# Dual_Power.net
KiCad netlist of a schematic drawn in Altium Designer
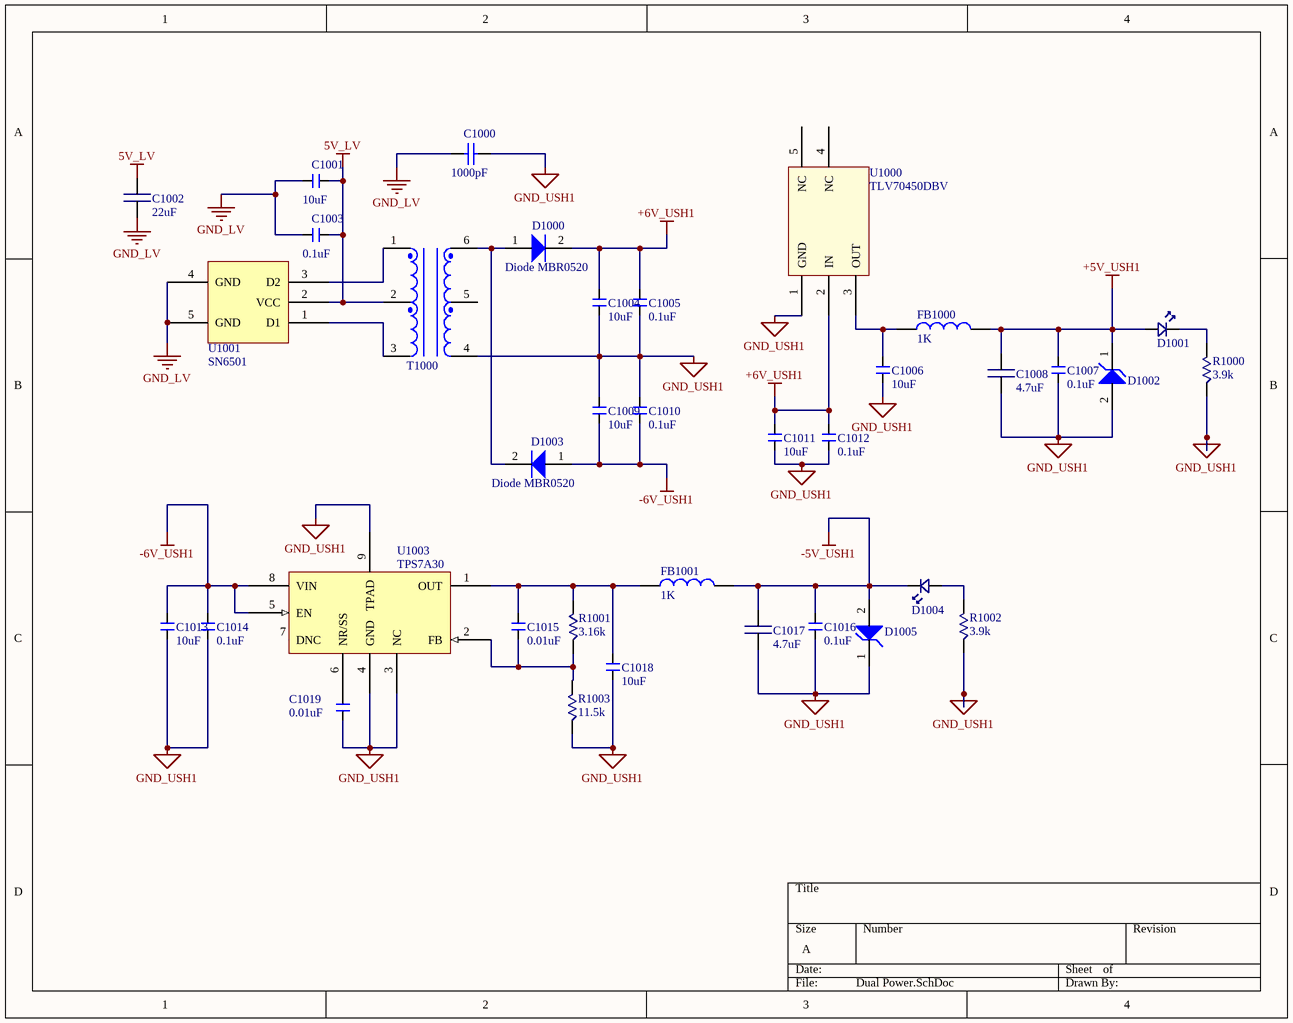
[diagram p0: Dual Power.SchDoc]

(export (version "E")
  (design (tool "Eeschema 10.0.6"))
  (components
    (comp (ref "C1000")
      (value "1000pF")
      (footprint "RAD-0.3")
      (description "CAP CER 1000PF 1KV Y5P RADIAL")
      (fields
        (field (name "PART") "1251PH-ND")
        (field (name "Comment") "Cap TH")
        (field (name "PUBLISHER") "Altium Limited")
      )
      (libsource (lib "Miscellaneous Devices") (part "Cap"))
    )
    (comp (ref "C1001")
      (value "10uF")
      (footprint "0603 (1608 Metric)")
      (description "CAP CER 10UF 35V X5R 0805")
      (fields (field (name "PART") "490-10515-1-ND") (field (name "Comment") "Cap 0603_new"))
      (libsource (lib "Library_Microgrid") (part "Cap 0603_new"))
    )
    (comp (ref "C1002")
      (value "22uF")
      (footprint "0805 (2012 metric)")
      (description "CAP CER 22UF 35V X5R 0805")
      (fields (field (name "PART") "445-14428-1-ND") (field (name "Comment") "Cap 0805"))
      (libsource (lib "Library_Microgrid") (part "Cap 0805"))
    )
    (comp (ref "C1003")
      (value "0.1uF")
      (footprint "0603 (1608 Metric)")
      (description "CAP CER 0.1UF 50V Y5V 0603")
      (fields (field (name "PART") "311-1343-6-ND") (field (name "Comment") "Cap 0603_new"))
      (libsource (lib "Library_Microgrid") (part "Cap 0603_new"))
    )
    (comp (ref "C1004")
      (value "10uF")
      (footprint "0603 (1608 Metric)")
      (description "CAP CER 10UF 35V X5R 0805")
      (fields (field (name "PART") "490-10515-1-ND") (field (name "Comment") "Cap 0603_new"))
      (libsource (lib "Library_Microgrid") (part "Cap 0603_new"))
    )
    (comp (ref "C1005")
      (value "0.1uF")
      (footprint "0603 (1608 Metric)")
      (description "CAP CER 0.1UF 50V Y5V 0603")
      (fields (field (name "PART") "311-1343-6-ND") (field (name "Comment") "Cap 0603_new"))
      (libsource (lib "Library_Microgrid") (part "Cap 0603_new"))
    )
    (comp (ref "C1006")
      (value "10uF")
      (footprint "0603 (1608 Metric)")
      (description "CAP CER 10UF 35V X5R 0805")
      (fields (field (name "PART") "490-10515-1-ND") (field (name "Comment") "Cap 0603_new"))
      (libsource (lib "Library_Microgrid") (part "Cap 0603_new"))
    )
    (comp (ref "C1007")
      (value "0.1uF")
      (footprint "0603 (1608 Metric)")
      (description "CAP CER 0.1UF 50V Y5V 0603")
      (fields (field (name "PART") "311-1343-6-ND") (field (name "Comment") "Cap 0603_new"))
      (libsource (lib "Library_Microgrid") (part "Cap 0603_new"))
    )
    (comp (ref "C1008")
      (value "4.7uF")
      (footprint "0805 (2012 metric)")
      (description "CAP CER 4.7UF 50V X5R 0805")
      (fields (field (name "PART") "445-5980-1-ND") (field (name "Comment") "Cap 0805"))
      (libsource (lib "Library_Microgrid") (part "Cap 0805"))
    )
    (comp (ref "C1009")
      (value "10uF")
      (footprint "0603 (1608 Metric)")
      (description "CAP CER 10UF 35V X5R 0805")
      (fields (field (name "PART") "490-10515-1-ND") (field (name "Comment") "Cap 0603_new"))
      (libsource (lib "Library_Microgrid") (part "Cap 0603_new"))
    )
    (comp (ref "C1010")
      (value "0.1uF")
      (footprint "0603 (1608 Metric)")
      (description "CAP CER 0.1UF 50V Y5V 0603")
      (fields (field (name "PART") "311-1343-6-ND") (field (name "Comment") "Cap 0603_new"))
      (libsource (lib "Library_Microgrid") (part "Cap 0603_new"))
    )
    (comp (ref "C1011")
      (value "10uF")
      (footprint "0603 (1608 Metric)")
      (description "CAP CER 10UF 35V X5R 0805")
      (fields (field (name "PART") "490-10515-1-ND") (field (name "Comment") "Cap 0603_new"))
      (libsource (lib "Library_Microgrid") (part "Cap 0603_new"))
    )
    (comp (ref "C1012")
      (value "0.1uF")
      (footprint "0603 (1608 Metric)")
      (description "CAP CER 0.1UF 50V Y5V 0603")
      (fields (field (name "PART") "311-1343-6-ND") (field (name "Comment") "Cap 0603_new"))
      (libsource (lib "Library_Microgrid") (part "Cap 0603_new"))
    )
    (comp (ref "C1013")
      (value "10uF")
      (footprint "0603 (1608 Metric)")
      (description "CAP CER 10UF 35V X5R 0805")
      (fields (field (name "PART") "490-10515-1-ND") (field (name "Comment") "Cap 0603_new"))
      (libsource (lib "Library_Microgrid") (part "Cap 0603_new"))
    )
    (comp (ref "C1014")
      (value "0.1uF")
      (footprint "0603 (1608 Metric)")
      (description "CAP CER 0.1UF 50V Y5V 0603")
      (fields (field (name "PART") "311-1343-6-ND") (field (name "Comment") "Cap 0603_new"))
      (libsource (lib "Library_Microgrid") (part "Cap 0603_new"))
    )
    (comp (ref "C1015")
      (value "0.01uF")
      (footprint "0603 (1608 Metric)")
      (description "CAP CER 10000PF 100V X7R 0603")
      (fields (field (name "PART") "478-7418-1-ND") (field (name "Comment") "Cap 0603_new"))
      (libsource (lib "Library_Microgrid") (part "Cap 0603_new"))
    )
    (comp (ref "C1016")
      (value "0.1uF")
      (footprint "0603 (1608 Metric)")
      (description "CAP CER 0.1UF 50V Y5V 0603")
      (fields (field (name "PART") "311-1343-6-ND") (field (name "Comment") "Cap 0603_new"))
      (libsource (lib "Library_Microgrid") (part "Cap 0603_new"))
    )
    (comp (ref "C1017")
      (value "4.7uF")
      (footprint "0805 (2012 metric)")
      (description "CAP CER 4.7UF 50V X5R 0805")
      (fields (field (name "PART") "445-5980-1-ND") (field (name "Comment") "Cap 0805"))
      (libsource (lib "Library_Microgrid") (part "Cap 0805"))
    )
    (comp (ref "C1018")
      (value "10uF")
      (footprint "0603 (1608 Metric)")
      (description "CAP CER 10UF 35V X5R 0805")
      (fields (field (name "PART") "490-10515-1-ND") (field (name "Comment") "Cap 0603_new"))
      (libsource (lib "Library_Microgrid") (part "Cap 0603_new"))
    )
    (comp (ref "C1019")
      (value "0.01uF")
      (footprint "0603 (1608 Metric)")
      (description "CAP CER 10000PF 100V X7R 0603")
      (fields (field (name "PART") "478-7418-1-ND") (field (name "Comment") "Cap 0603_new"))
      (libsource (lib "Library_Microgrid") (part "Cap 0603_new"))
    )
    (comp (ref "D1000")
      (value "Diode MBR0520")
      (footprint "SOD-123")
      (description "DIODE SCHOTTKY 20V 500MA SOD123")
      (fields (field (name "PART") "MBR0520LT1GOSCT-ND"))
      (libsource (lib "Library_Microgrid") (part "Diode MBR0520"))
    )
    (comp (ref "D1001")
      (value "LED")
      (footprint "0805 (2012 Metric) Diode")
      (description "LED 0805")
      (libsource (lib "Library_Microgrid") (part "LED"))
    )
    (comp (ref "D1002")
      (value "Diode Zener POWERDI123")
      (footprint "POWERDI")
      (description "DIODE ZENER POWERDI123")
      (libsource (lib "Library_Microgrid") (part "Diode Zener POWERDI123"))
    )
    (comp (ref "D1003")
      (value "Diode MBR0520")
      (footprint "SOD-123")
      (description "DIODE SCHOTTKY 20V 500MA SOD123")
      (fields (field (name "PART") "MBR0520LT1GOSCT-ND"))
      (libsource (lib "Library_Microgrid") (part "Diode MBR0520"))
    )
    (comp (ref "D1004")
      (value "LED")
      (footprint "0805 (2012 Metric) Diode")
      (description "LED 0805")
      (libsource (lib "Library_Microgrid") (part "LED"))
    )
    (comp (ref "D1005")
      (value "Diode Zener POWERDI123")
      (footprint "POWERDI")
      (description "DIODE ZENER POWERDI123")
      (libsource (lib "Library_Microgrid") (part "Diode Zener POWERDI123"))
    )
    (comp (ref "FB1000")
      (value "1K")
      (footprint "0603 (1608 Metric)")
      (description "FERRITE BEAD 1 KOHM 0603 1LN")
      (fields (field (name "PART") "445-8672-1-ND") (field (name "Comment") "Ferrite bead"))
      (libsource (lib "Library_Microgrid") (part "Ferrite bead"))
    )
    (comp (ref "FB1001")
      (value "1K")
      (footprint "0603 (1608 Metric)")
      (description "FERRITE BEAD 1 KOHM 0603 1LN")
      (fields (field (name "PART") "445-8672-1-ND") (field (name "Comment") "Ferrite bead"))
      (libsource (lib "Library_Microgrid") (part "Ferrite bead"))
    )
    (comp (ref "R1000")
      (value "3.9k")
      (footprint "0603 (1608 Metric)")
      (description "RES SMD 3.9K OHM 5% 1/10W 0603")
      (fields (field (name "PART") "541-3.9KGCT-ND") (field (name "Comment") "Resistor 0603"))
      (libsource (lib "Library_Microgrid") (part "Resistor 0603"))
    )
    (comp (ref "R1001")
      (value "3.16k")
      (footprint "0603 (1608 Metric)")
      (description "RES SMD 3.16K OHM 1% 1/10W 0603")
      (fields (field (name "PART") "311-3.16KHRCT-ND") (field (name "Comment") "Resistor 0603"))
      (libsource (lib "Library_Microgrid") (part "Resistor 0603"))
    )
    (comp (ref "R1002")
      (value "3.9k")
      (footprint "0603 (1608 Metric)")
      (description "RES SMD 3.9K OHM 5% 1/10W 0603")
      (fields (field (name "PART") "541-3.9KGCT-ND") (field (name "Comment") "Resistor 0603"))
      (libsource (lib "Library_Microgrid") (part "Resistor 0603"))
    )
    (comp (ref "R1003")
      (value "11.5k")
      (footprint "0603 (1608 Metric)")
      (description "RES SMD 11.5K OHM 1% 1/10W 0603")
      (fields (field (name "PART") "541-11.5KHCT-ND") (field (name "Comment") "Resistor 0603"))
      (libsource (lib "Library_Microgrid") (part "Resistor 0603"))
    )
    (comp (ref "T1000")
      (value "750313769")
      (footprint "Xmr SN6501")
      (description "TRANSFORMER SMD TR1.7 SN6501")
      (fields (field (name "PART") "1297-1107-1-ND"))
      (libsource (lib "Library_Microgrid") (part "750313769"))
    )
    (comp (ref "U1000")
      (value "TLV70450DBV")
      (footprint "SOT23-5")
      (description "IC REG LDO 5V 0.15A SOT23-5")
      (fields (field (name "PART") "296-39287-1-ND"))
      (libsource (lib "Library_Microgrid") (part "TLV70450DBV"))
    )
    (comp (ref "U1001")
      (value "SN6501")
      (footprint "SOT23-5")
      (description "IC REG CONV PWR SUPPLIES SOT23-5")
      (libsource (lib "Library_Microgrid") (part "SN6501"))
    )
    (comp (ref "U1003")
      (value "TPS7A30")
      (footprint "8-TSSOP")
      (description "IC REG LDO NEG ADJ 0.2A 8MSOP")
      (fields (field (name "PART") "296-27750-1-ND"))
      (libsource (lib "Library_Microgrid") (part "TPS7A30"))
    )
  )
  (nets
    (net (code "1") (name "+5V_USH1") (class "Default")
      (node (ref "C1007") (pin "2") (pinfunction "OUT_2") (pintype "passive"))
      (node (ref "C1008") (pin "2") (pinfunction "OUT_2") (pintype "passive"))
      (node (ref "D1001") (pin "A") (pinfunction "A_A") (pintype "passive"))
      (node (ref "D1002") (pin "1") (pinfunction "Anode_1") (pintype "passive"))
      (node (ref "FB1000") (pin "2") (pinfunction "OUT_2") (pintype "passive"))
    )
    (net (code "2") (name "+6V_USH1") (class "Default")
      (node (ref "C1004") (pin "2") (pinfunction "OUT_2") (pintype "passive"))
      (node (ref "C1005") (pin "2") (pinfunction "OUT_2") (pintype "passive"))
      (node (ref "C1011") (pin "2") (pinfunction "OUT_2") (pintype "passive"))
      (node (ref "C1012") (pin "2") (pinfunction "OUT_2") (pintype "passive"))
      (node (ref "D1000") (pin "2") (pinfunction "Anode_2") (pintype "passive"))
      (node (ref "U1000") (pin "2") (pinfunction "IN_2") (pintype "passive"))
    )
    (net (code "3") (name "-5V_USH1") (class "Default")
      (node (ref "C1016") (pin "2") (pinfunction "OUT_2") (pintype "passive"))
      (node (ref "C1017") (pin "2") (pinfunction "OUT_2") (pintype "passive"))
      (node (ref "D1004") (pin "K") (pinfunction "K_K") (pintype "passive"))
      (node (ref "D1005") (pin "2") (pinfunction "Anode_2") (pintype "passive"))
      (node (ref "FB1001") (pin "2") (pinfunction "OUT_2") (pintype "passive"))
    )
    (net (code "4") (name "-6V_USH1") (class "Default")
      (node (ref "C1009") (pin "1") (pinfunction "OUT_1") (pintype "passive"))
      (node (ref "C1010") (pin "1") (pinfunction "OUT_1") (pintype "passive"))
      (node (ref "C1013") (pin "2") (pinfunction "OUT_2") (pintype "passive"))
      (node (ref "C1014") (pin "2") (pinfunction "OUT_2") (pintype "passive"))
      (node (ref "D1003") (pin "1") (pinfunction "Anode_1") (pintype "passive"))
      (node (ref "U1003") (pin "5") (pinfunction "EN_5") (pintype "input"))
      (node (ref "U1003") (pin "8") (pinfunction "VIN_8") (pintype "power_in"))
    )
    (net (code "5") (name "5V_LV") (class "Default")
      (node (ref "C1001") (pin "2") (pinfunction "OUT_2") (pintype "passive"))
      (node (ref "C1002") (pin "2") (pinfunction "OUT_2") (pintype "passive"))
      (node (ref "C1003") (pin "2") (pinfunction "OUT_2") (pintype "passive"))
      (node (ref "T1000") (pin "2") (pinfunction "1_2") (pintype "passive"))
      (node (ref "U1001") (pin "2") (pinfunction "VCC_2") (pintype "passive"))
    )
    (net (code "6") (name "GND_LV") (class "Default")
      (node (ref "C1000") (pin "1") (pinfunction "1_1") (pintype "passive"))
      (node (ref "C1001") (pin "1") (pinfunction "OUT_1") (pintype "passive"))
      (node (ref "C1002") (pin "1") (pinfunction "OUT_1") (pintype "passive"))
      (node (ref "C1003") (pin "1") (pinfunction "OUT_1") (pintype "passive"))
      (node (ref "U1001") (pin "4") (pinfunction "GND_4") (pintype "passive"))
      (node (ref "U1001") (pin "5") (pinfunction "GND_5") (pintype "passive"))
    )
    (net (code "7") (name "GND_USH1") (class "Default")
      (node (ref "C1000") (pin "2") (pinfunction "2_2") (pintype "passive"))
      (node (ref "C1004") (pin "1") (pinfunction "OUT_1") (pintype "passive"))
      (node (ref "C1005") (pin "1") (pinfunction "OUT_1") (pintype "passive"))
      (node (ref "C1006") (pin "1") (pinfunction "OUT_1") (pintype "passive"))
      (node (ref "C1007") (pin "1") (pinfunction "OUT_1") (pintype "passive"))
      (node (ref "C1008") (pin "1") (pinfunction "OUT_1") (pintype "passive"))
      (node (ref "C1009") (pin "2") (pinfunction "OUT_2") (pintype "passive"))
      (node (ref "C1010") (pin "2") (pinfunction "OUT_2") (pintype "passive"))
      (node (ref "C1011") (pin "1") (pinfunction "OUT_1") (pintype "passive"))
      (node (ref "C1012") (pin "1") (pinfunction "OUT_1") (pintype "passive"))
      (node (ref "C1013") (pin "1") (pinfunction "OUT_1") (pintype "passive"))
      (node (ref "C1014") (pin "1") (pinfunction "OUT_1") (pintype "passive"))
      (node (ref "C1016") (pin "1") (pinfunction "OUT_1") (pintype "passive"))
      (node (ref "C1017") (pin "1") (pinfunction "OUT_1") (pintype "passive"))
      (node (ref "C1018") (pin "1") (pinfunction "OUT_1") (pintype "passive"))
      (node (ref "C1019") (pin "1") (pinfunction "OUT_1") (pintype "passive"))
      (node (ref "D1002") (pin "2") (pinfunction "Anode_2") (pintype "passive"))
      (node (ref "D1005") (pin "1") (pinfunction "Anode_1") (pintype "passive"))
      (node (ref "R1000") (pin "1") (pinfunction "A_1") (pintype "passive"))
      (node (ref "R1002") (pin "1") (pinfunction "A_1") (pintype "passive"))
      (node (ref "R1003") (pin "1") (pinfunction "A_1") (pintype "passive"))
      (node (ref "T1000") (pin "4") (pinfunction "1_4") (pintype "passive"))
      (node (ref "U1000") (pin "1") (pinfunction "GND_1") (pintype "passive"))
      (node (ref "U1003") (pin "3") (pinfunction "NC_3") (pintype "passive"))
      (node (ref "U1003") (pin "4") (pinfunction "GND_4") (pintype "power_in"))
      (node (ref "U1003") (pin "9") (pinfunction "TPAD_9") (pintype "power_in"))
    )
    (net (code "8") (name "Net-(D1000-Anode-Pad1)") (class "Default")
      (node (ref "D1000") (pin "1") (pinfunction "Anode_1") (pintype "passive"))
      (node (ref "D1003") (pin "2") (pinfunction "Anode_2") (pintype "passive"))
      (node (ref "T1000") (pin "6") (pinfunction "1_6") (pintype "passive"))
    )
    (net (code "9") (name "Net-(D1001-PadK)") (class "Default")
      (node (ref "D1001") (pin "K") (pinfunction "K_K") (pintype "passive"))
      (node (ref "R1000") (pin "2") (pinfunction "A_2") (pintype "passive"))
    )
    (net (code "10") (name "Net-(D1004-PadA)") (class "Default")
      (node (ref "D1004") (pin "A") (pinfunction "A_A") (pintype "passive"))
      (node (ref "R1002") (pin "2") (pinfunction "A_2") (pintype "passive"))
    )
    (net (code "11") (name "Net-(U1000-OUT)") (class "Default")
      (node (ref "C1006") (pin "2") (pinfunction "OUT_2") (pintype "passive"))
      (node (ref "FB1000") (pin "1") (pinfunction "OUT_1") (pintype "passive"))
      (node (ref "U1000") (pin "3") (pinfunction "OUT_3") (pintype "passive"))
    )
    (net (code "12") (name "Net-(U1001-D1)") (class "Default")
      (node (ref "T1000") (pin "3") (pinfunction "1_3") (pintype "passive"))
      (node (ref "U1001") (pin "1") (pinfunction "D1_1") (pintype "passive"))
    )
    (net (code "13") (name "Net-(U1001-D2)") (class "Default")
      (node (ref "T1000") (pin "1") (pinfunction "1_1") (pintype "passive"))
      (node (ref "U1001") (pin "3") (pinfunction "D2_3") (pintype "passive"))
    )
    (net (code "14") (name "Net-(U1003-FB)") (class "Default")
      (node (ref "C1015") (pin "2") (pinfunction "OUT_2") (pintype "passive"))
      (node (ref "R1001") (pin "1") (pinfunction "A_1") (pintype "passive"))
      (node (ref "R1003") (pin "2") (pinfunction "A_2") (pintype "passive"))
      (node (ref "U1003") (pin "2") (pinfunction "FB_2") (pintype "input"))
    )
    (net (code "15") (name "Net-(U1003-NR{slash}SS)") (class "Default")
      (node (ref "C1019") (pin "2") (pinfunction "OUT_2") (pintype "passive"))
      (node (ref "U1003") (pin "6") (pinfunction "NR/SS_6") (pintype "power_in"))
    )
    (net (code "16") (name "Net-(U1003-OUT)") (class "Default")
      (node (ref "C1015") (pin "1") (pinfunction "OUT_1") (pintype "passive"))
      (node (ref "C1018") (pin "2") (pinfunction "OUT_2") (pintype "passive"))
      (node (ref "FB1001") (pin "1") (pinfunction "OUT_1") (pintype "passive"))
      (node (ref "R1001") (pin "2") (pinfunction "A_2") (pintype "passive"))
      (node (ref "U1003") (pin "1") (pinfunction "OUT_1") (pintype "passive"))
    )
    (net (code "17") (name "unconnected-(T1000-1-Pad5)") (class "Default")
      (node (ref "T1000") (pin "5") (pinfunction "1_5") (pintype "passive"))
    )
    (net (code "18") (name "unconnected-(U1000-NC-Pad4)") (class "Default")
      (node (ref "U1000") (pin "4") (pinfunction "NC_4") (pintype "passive"))
    )
    (net (code "19") (name "unconnected-(U1000-NC-Pad5)") (class "Default")
      (node (ref "U1000") (pin "5") (pinfunction "NC_5") (pintype "passive"))
    )
    (net (code "20") (name "unconnected-(U1003-DNC-Pad7)") (class "Default")
      (node (ref "U1003") (pin "7") (pinfunction "DNC_7") (pintype "passive"))
    )
  )
)
